# FT4222_Schematic.net
KiCad netlist of a schematic drawn in Altium Designer
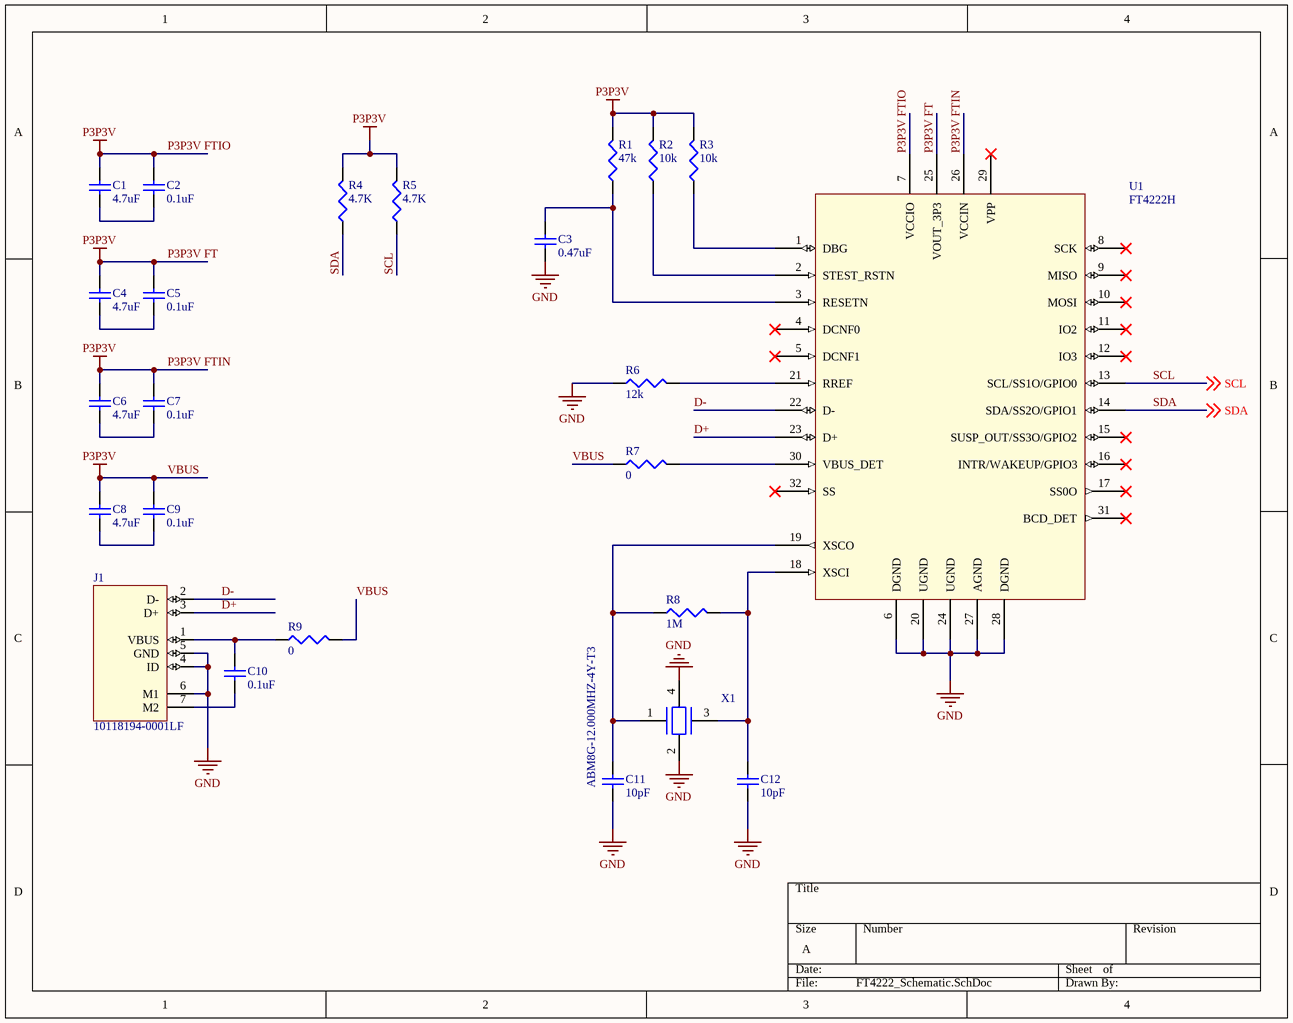
[diagram p0: FT4222_Schematic.SchDoc]

(export (version "E")
  (design (tool "Eeschema 10.0.6"))
  (components
    (comp (ref "C1")
      (value "4.7uF")
      (footprint "CAPC0603X33N")
      (description "CAP CER 4.7UF 16V X5R 0402")
      (fields (field (name "MFGPARTNO") "0402YD475MAT2A") (field (name "MFG") "AVX"))
      (libsource (lib "SLA3000-FPGA[4086]") (part "CMP-00798-A.1"))
    )
    (comp (ref "C2")
      (value "0.1uF")
      (footprint "CAPC0603X33N")
      (description "CAP CER 0.1UF 25V X7R 0402")
      (fields (field (name "SLA PART NO") "SL00150") (field (name "MFG") "TDK"))
      (libsource (lib "SLA3000-FPGA[4086]") (part "CMP-00496-A.6"))
    )
    (comp (ref "C3")
      (value "0.47uF")
      (footprint "CAPC1608X90")
      (description "CAP CER 0.47UF 16V 10% X7R 0603")
      (fields (field (name "SLA PART NO") "SL00008") (field (name "MFG") "Kemet"))
      (libsource (lib "SLA3000-FPGA[4086]") (part "CMP-00498-A.6"))
    )
    (comp (ref "C4")
      (value "4.7uF")
      (footprint "CAPC0603X33N")
      (description "CAP CER 4.7UF 16V X5R 0402")
      (fields (field (name "MFGPARTNO") "0402YD475MAT2A") (field (name "MFG") "AVX"))
      (libsource (lib "SLA3000-FPGA[4086]") (part "CMP-00798-A.1"))
    )
    (comp (ref "C5")
      (value "0.1uF")
      (footprint "CAPC0603X33N")
      (description "CAP CER 0.1UF 25V X7R 0402")
      (fields (field (name "SLA PART NO") "SL00150") (field (name "MFG") "TDK"))
      (libsource (lib "SLA3000-FPGA[4086]") (part "CMP-00496-A.6"))
    )
    (comp (ref "C6")
      (value "4.7uF")
      (footprint "CAPC0603X33N")
      (description "CAP CER 4.7UF 16V X5R 0402")
      (fields (field (name "MFGPARTNO") "0402YD475MAT2A") (field (name "MFG") "AVX"))
      (libsource (lib "SLA3000-FPGA[4086]") (part "CMP-00798-A.1"))
    )
    (comp (ref "C7")
      (value "0.1uF")
      (footprint "CAPC0603X33N")
      (description "CAP CER 0.1UF 25V X7R 0402")
      (fields (field (name "SLA PART NO") "SL00150") (field (name "MFG") "TDK"))
      (libsource (lib "SLA3000-FPGA[4086]") (part "CMP-00496-A.6"))
    )
    (comp (ref "C8")
      (value "4.7uF")
      (footprint "CAPC0603X33N")
      (description "CAP CER 4.7UF 16V X5R 0402")
      (fields (field (name "MFGPARTNO") "0402YD475MAT2A") (field (name "MFG") "AVX"))
      (libsource (lib "SLA3000-FPGA[4086]") (part "CMP-00798-A.1"))
    )
    (comp (ref "C9")
      (value "0.1uF")
      (footprint "CAPC0603X33N")
      (description "CAP CER 0.1UF 25V X7R 0402")
      (fields (field (name "SLA PART NO") "SL00150") (field (name "MFG") "TDK"))
      (libsource (lib "SLA3000-FPGA[4086]") (part "CMP-00496-A.6"))
    )
    (comp (ref "C10")
      (value "0.1uF")
      (footprint "INDC1005X45")
      (description "CAP CER 0.1UF 25V X7R 0402")
      (fields (field (name "SLA PART NO") "SL00150") (field (name "MFG") "TDK"))
      (libsource (lib "SLA3000-FPGA[4086]") (part "CMP-00496-A.6"))
    )
    (comp (ref "C11")
      (value "10pF")
      (footprint "INDC1005X45")
      (description "CAP CER 10PF 50V C0G/NP0 0402")
      (fields (field (name "MFGPARTNO") "GCM1555C1H100FA16D") (field (name "MFG") "Murata"))
      (libsource (lib "SLA3000-FPGA[4086]") (part "CMP-00614-A.1"))
    )
    (comp (ref "C12")
      (value "10pF")
      (footprint "INDC1005X45")
      (description "CAP CER 10PF 50V C0G/NP0 0402")
      (fields (field (name "MFGPARTNO") "GCM1555C1H100FA16D") (field (name "MFG") "Murata"))
      (libsource (lib "SLA3000-FPGA[4086]") (part "CMP-00614-A.1"))
    )
    (comp (ref "J1")
      (value "10118194-0001LF")
      (footprint "AMPHENOL_10118194-0001LF")
      (description "10118194-0001LF CONN USB MICRO B RECPT THRU-SMT R/A")
      (fields (field (name "MFG") "Amphenol"))
      (libsource (lib "SLA3000-FPGA[4086]") (part "CMP-00755-A.2"))
    )
    (comp (ref "R1")
      (value "47k")
      (footprint "RES_ERJU02F1241X")
      (description "RES SMD 47K OHM 1% 1/10W 0402")
      (fields (field (name "MFG") "Panasonic") (field (name "MFGPARTNO") "ERJ-U02F4702X"))
      (libsource (lib "SLA3000-FPGA[4086]") (part "CMP-00852-A.2"))
    )
    (comp (ref "R2")
      (value "10k")
      (footprint "RES_ERJU02F1241X")
      (description "RES SMD 10K OHM 1% 1/10W 0402")
      (fields (field (name "SLA PART NO") "SL00225") (field (name "MFG") "Panasonic"))
      (libsource (lib "SLA3000-FPGA[4086]") (part "CMP-00396-A.9"))
    )
    (comp (ref "R3")
      (value "10k")
      (footprint "RES_ERJU02F1241X")
      (description "RES SMD 10K OHM 1% 1/10W 0402")
      (fields (field (name "SLA PART NO") "SL00225") (field (name "MFG") "Panasonic"))
      (libsource (lib "SLA3000-FPGA[4086]") (part "CMP-00396-A.9"))
    )
    (comp (ref "R4")
      (value "4.7K")
      (footprint "RES_ERJU02F1241X")
      (description "RES SMD 4K7 OHM 1% 1/16W 0402")
      (fields (field (name "MFGPARTNO") "RC0402FR-074K7P") (field (name "MFG") "Yageo"))
      (libsource (lib "SLA3000-FPGA[4086]") (part "CMP-00761-A.1"))
    )
    (comp (ref "R5")
      (value "4.7K")
      (footprint "RES_ERJU02F1241X")
      (description "RES SMD 4K7 OHM 1% 1/16W 0402")
      (fields (field (name "MFGPARTNO") "RC0402FR-074K7P") (field (name "MFG") "Yageo"))
      (libsource (lib "SLA3000-FPGA[4086]") (part "CMP-00761-A.1"))
    )
    (comp (ref "R6")
      (value "12k")
      (footprint "RES_ERJU02F1241X")
      (description "RES SMD 12K OHM 1% 1/16W 0402")
      (fields (field (name "MFG") "Yageo") (field (name "MFGPARTNO") "RC0402FR-0712KL"))
      (libsource (lib "SLA3000-FPGA[4086]") (part "CMP-00612-A.1"))
    )
    (comp (ref "R7")
      (value "0")
      (footprint "RESC1608X50N")
      (description "RES SMD 0.0OHM JUMPER 1/10W 0603")
      (fields (field (name "MFG") "Panasonic") (field (name "MFGPARTNO") "ERJ-3GEY0R00V"))
      (libsource (lib "SLA3000-FPGA[4086]") (part "CMP-00342-A.7"))
    )
    (comp (ref "R8")
      (value "1M")
      (footprint "RES_ERJU02F1241X")
      (description "RES SMD 1M OHM 1% 1/10W 0402")
      (fields (field (name "MFGPARTNO") "ERJ-2RKF1004X") (field (name "SLA PART NO") "SL00141"))
      (libsource (lib "SLA3000-FPGA[4086]") (part "CMP-00430-A.9"))
    )
    (comp (ref "R9")
      (value "0")
      (footprint "RES_ERJU02F1241X")
      (description "RES SMD 0.0OHM JUMPER 1/10W 0402")
      (fields (field (name "SLA PART NO") "SL00128") (field (name "MFGPARTNO") "ERJ-2GE0R00X"))
      (libsource (lib "SLA3000-FPGA[4086]") (part "CMP-00341-A.9"))
    )
    (comp (ref "U1")
      (value "FT4222H")
      (footprint "QFP50P1200X1200X160-64N")
      (description "FT4222H USB2.0 TO QUADSPI/I2C BRIDGE IC VQFN-32")
      (fields (field (name "MFG") "FTDI"))
      (libsource (lib "SLA3000-FPGA[4086]") (part "CMP-00851-A.3"))
    )
    (comp (ref "X1")
      (value "ABM8G-12.000MHZ-4Y-T3")
      (footprint "OSCSC320X250X100N")
      (description "CRYSTAL 12.0000MHZ 10PF SMD")
      (fields (field (name "MFG") "Abracon"))
      (libsource (lib "SLA3000-FPGA[4086]") (part "CMP-00613-A.2"))
    )
  )
  (nets
    (net (code "1") (name "/D+") (class "Default")
      (node (ref "J1") (pin "3") (pinfunction "D+_3") (pintype "bidirectional"))
      (node (ref "U1") (pin "23") (pinfunction "D+_23") (pintype "bidirectional"))
    )
    (net (code "2") (name "/D-") (class "Default")
      (node (ref "J1") (pin "2") (pinfunction "D-_2") (pintype "bidirectional"))
      (node (ref "U1") (pin "22") (pinfunction "D-_22") (pintype "bidirectional"))
    )
    (net (code "3") (name "GND") (class "Default")
      (node (ref "C11") (pin "1") (pinfunction "1_1") (pintype "passive"))
      (node (ref "C12") (pin "1") (pinfunction "1_1") (pintype "passive"))
      (node (ref "C3") (pin "1") (pinfunction "1_1") (pintype "passive"))
      (node (ref "J1") (pin "4") (pinfunction "ID_4") (pintype "bidirectional"))
      (node (ref "J1") (pin "5") (pinfunction "GND_5") (pintype "bidirectional"))
      (node (ref "J1") (pin "6") (pinfunction "M1_6") (pintype "power_in"))
      (node (ref "R6") (pin "1") (pinfunction "1_1") (pintype "passive"))
      (node (ref "U1") (pin "20") (pinfunction "UGND_20") (pintype "power_in"))
      (node (ref "U1") (pin "24") (pinfunction "UGND_24") (pintype "power_in"))
      (node (ref "U1") (pin "27") (pinfunction "AGND_27") (pintype "power_in"))
      (node (ref "U1") (pin "28") (pinfunction "DGND_28") (pintype "power_in"))
      (node (ref "U1") (pin "6") (pinfunction "DGND_6") (pintype "power_in"))
      (node (ref "X1") (pin "2") (pinfunction "GND_2") (pintype "power_in"))
      (node (ref "X1") (pin "4") (pinfunction "GND_4") (pintype "power_in"))
    )
    (net (code "4") (name "Net-(C1-Pad1)") (class "Default")
      (node (ref "C1") (pin "1") (pinfunction "1_1") (pintype "passive"))
      (node (ref "C2") (pin "1") (pinfunction "1_1") (pintype "passive"))
    )
    (net (code "5") (name "Net-(C4-Pad1)") (class "Default")
      (node (ref "C4") (pin "1") (pinfunction "1_1") (pintype "passive"))
      (node (ref "C5") (pin "1") (pinfunction "1_1") (pintype "passive"))
    )
    (net (code "6") (name "Net-(C6-Pad1)") (class "Default")
      (node (ref "C6") (pin "1") (pinfunction "1_1") (pintype "passive"))
      (node (ref "C7") (pin "1") (pinfunction "1_1") (pintype "passive"))
    )
    (net (code "7") (name "Net-(C8-Pad1)") (class "Default")
      (node (ref "C8") (pin "1") (pinfunction "1_1") (pintype "passive"))
      (node (ref "C9") (pin "1") (pinfunction "1_1") (pintype "passive"))
    )
    (net (code "8") (name "Net-(J1-M2)") (class "Default")
      (node (ref "C10") (pin "1") (pinfunction "1_1") (pintype "passive"))
      (node (ref "J1") (pin "7") (pinfunction "M2_7") (pintype "power_in"))
    )
    (net (code "9") (name "Net-(J1-VBUS)") (class "Default")
      (node (ref "C10") (pin "2") (pinfunction "2_2") (pintype "passive"))
      (node (ref "J1") (pin "1") (pinfunction "VBUS_1") (pintype "bidirectional"))
      (node (ref "R9") (pin "1") (pinfunction "1_1") (pintype "passive"))
    )
    (net (code "10") (name "Net-(U1-DBG)") (class "Default")
      (node (ref "R3") (pin "1") (pinfunction "1_1") (pintype "passive"))
      (node (ref "U1") (pin "1") (pinfunction "DBG_1") (pintype "bidirectional"))
    )
    (net (code "11") (name "Net-(U1-RESETN)") (class "Default")
      (node (ref "C3") (pin "2") (pinfunction "2_2") (pintype "passive"))
      (node (ref "R1") (pin "1") (pinfunction "1_1") (pintype "passive"))
      (node (ref "U1") (pin "3") (pinfunction "RESETN_3") (pintype "input"))
    )
    (net (code "12") (name "Net-(U1-RREF)") (class "Default")
      (node (ref "R6") (pin "2") (pinfunction "2_2") (pintype "passive"))
      (node (ref "U1") (pin "21") (pinfunction "RREF_21") (pintype "input"))
    )
    (net (code "13") (name "Net-(U1-STEST_RSTN)") (class "Default")
      (node (ref "R2") (pin "1") (pinfunction "1_1") (pintype "passive"))
      (node (ref "U1") (pin "2") (pinfunction "STEST_RSTN_2") (pintype "input"))
    )
    (net (code "14") (name "Net-(U1-VBUS_DET)") (class "Default")
      (node (ref "R7") (pin "2") (pinfunction "2_2") (pintype "passive"))
      (node (ref "U1") (pin "30") (pinfunction "VBUS_DET_30") (pintype "input"))
    )
    (net (code "15") (name "Net-(U1-XSCI)") (class "Default")
      (node (ref "C12") (pin "2") (pinfunction "2_2") (pintype "passive"))
      (node (ref "R8") (pin "2") (pinfunction "2_2") (pintype "passive"))
      (node (ref "U1") (pin "18") (pinfunction "XSCI_18") (pintype "input"))
      (node (ref "X1") (pin "3") (pinfunction "OSC2_3") (pintype "passive"))
    )
    (net (code "16") (name "Net-(U1-XSCO)") (class "Default")
      (node (ref "C11") (pin "2") (pinfunction "2_2") (pintype "passive"))
      (node (ref "R8") (pin "1") (pinfunction "1_1") (pintype "passive"))
      (node (ref "U1") (pin "19") (pinfunction "XSCO_19") (pintype "output"))
      (node (ref "X1") (pin "1") (pinfunction "OSC1_1") (pintype "passive"))
    )
    (net (code "17") (name "P3P3V") (class "Default")
      (node (ref "C1") (pin "2") (pinfunction "2_2") (pintype "passive"))
      (node (ref "C2") (pin "2") (pinfunction "2_2") (pintype "passive"))
      (node (ref "C4") (pin "2") (pinfunction "2_2") (pintype "passive"))
      (node (ref "C5") (pin "2") (pinfunction "2_2") (pintype "passive"))
      (node (ref "C6") (pin "2") (pinfunction "2_2") (pintype "passive"))
      (node (ref "C7") (pin "2") (pinfunction "2_2") (pintype "passive"))
      (node (ref "C8") (pin "2") (pinfunction "2_2") (pintype "passive"))
      (node (ref "C9") (pin "2") (pinfunction "2_2") (pintype "passive"))
      (node (ref "R1") (pin "2") (pinfunction "2_2") (pintype "passive"))
      (node (ref "R2") (pin "2") (pinfunction "2_2") (pintype "passive"))
      (node (ref "R3") (pin "2") (pinfunction "2_2") (pintype "passive"))
      (node (ref "R4") (pin "2") (pinfunction "2_2") (pintype "passive"))
      (node (ref "R5") (pin "2") (pinfunction "2_2") (pintype "passive"))
      (node (ref "R7") (pin "1") (pinfunction "1_1") (pintype "passive"))
      (node (ref "R9") (pin "2") (pinfunction "2_2") (pintype "passive"))
      (node (ref "U1") (pin "25") (pinfunction "VOUT_3P3_25") (pintype "power_in"))
      (node (ref "U1") (pin "26") (pinfunction "VCCIN_26") (pintype "power_in"))
      (node (ref "U1") (pin "7") (pinfunction "VCCIO_7") (pintype "power_in"))
    )
    (net (code "18") (name "SCL") (class "Default")
      (node (ref "R5") (pin "1") (pinfunction "1_1") (pintype "passive"))
      (node (ref "U1") (pin "13") (pinfunction "SCL/SS1O/GPIO0_13") (pintype "bidirectional"))
    )
    (net (code "19") (name "SDA") (class "Default")
      (node (ref "R4") (pin "1") (pinfunction "1_1") (pintype "passive"))
      (node (ref "U1") (pin "14") (pinfunction "SDA/SS2O/GPIO1_14") (pintype "bidirectional"))
    )
    (net (code "20") (name "unconnected-(U1-BCD_DET-Pad31)") (class "Default")
      (node (ref "U1") (pin "31") (pinfunction "BCD_DET_31") (pintype "output+no_connect"))
    )
    (net (code "21") (name "unconnected-(U1-DCNF0-Pad4)") (class "Default")
      (node (ref "U1") (pin "4") (pinfunction "DCNF0_4") (pintype "input+no_connect"))
    )
    (net (code "22") (name "unconnected-(U1-DCNF1-Pad5)") (class "Default")
      (node (ref "U1") (pin "5") (pinfunction "DCNF1_5") (pintype "input+no_connect"))
    )
    (net (code "23") (name "unconnected-(U1-INTR{slash}WAKEUP{slash}GPIO3-Pad16)") (class "Default")
      (node (ref "U1") (pin "16") (pinfunction "INTR/WAKEUP/GPIO3_16") (pintype "bidirectional+no_connect"))
    )
    (net (code "24") (name "unconnected-(U1-IO2-Pad11)") (class "Default")
      (node (ref "U1") (pin "11") (pinfunction "IO2_11") (pintype "bidirectional+no_connect"))
    )
    (net (code "25") (name "unconnected-(U1-IO3-Pad12)") (class "Default")
      (node (ref "U1") (pin "12") (pinfunction "IO3_12") (pintype "bidirectional+no_connect"))
    )
    (net (code "26") (name "unconnected-(U1-MISO-Pad9)") (class "Default")
      (node (ref "U1") (pin "9") (pinfunction "MISO_9") (pintype "bidirectional+no_connect"))
    )
    (net (code "27") (name "unconnected-(U1-MOSI-Pad10)") (class "Default")
      (node (ref "U1") (pin "10") (pinfunction "MOSI_10") (pintype "bidirectional+no_connect"))
    )
    (net (code "28") (name "unconnected-(U1-SCK-Pad8)") (class "Default")
      (node (ref "U1") (pin "8") (pinfunction "SCK_8") (pintype "bidirectional+no_connect"))
    )
    (net (code "29") (name "unconnected-(U1-SS-Pad32)") (class "Default")
      (node (ref "U1") (pin "32") (pinfunction "SS_32") (pintype "input+no_connect"))
    )
    (net (code "30") (name "unconnected-(U1-SS0O-Pad17)") (class "Default")
      (node (ref "U1") (pin "17") (pinfunction "SS0O_17") (pintype "output+no_connect"))
    )
    (net (code "31") (name "unconnected-(U1-SUSP_OUT{slash}SS3O{slash}GPIO2-Pad15)") (class "Default")
      (node (ref "U1") (pin "15") (pinfunction "SUSP_OUT/SS3O/GPIO2_15") (pintype "bidirectional+no_connect"))
    )
    (net (code "32") (name "unconnected-(U1-VPP-Pad29)") (class "Default")
      (node (ref "U1") (pin "29") (pinfunction "VPP_29") (pintype "power_in+no_connect"))
    )
  )
)
